# Example.net
KiCad netlist of a schematic drawn in EAGLE
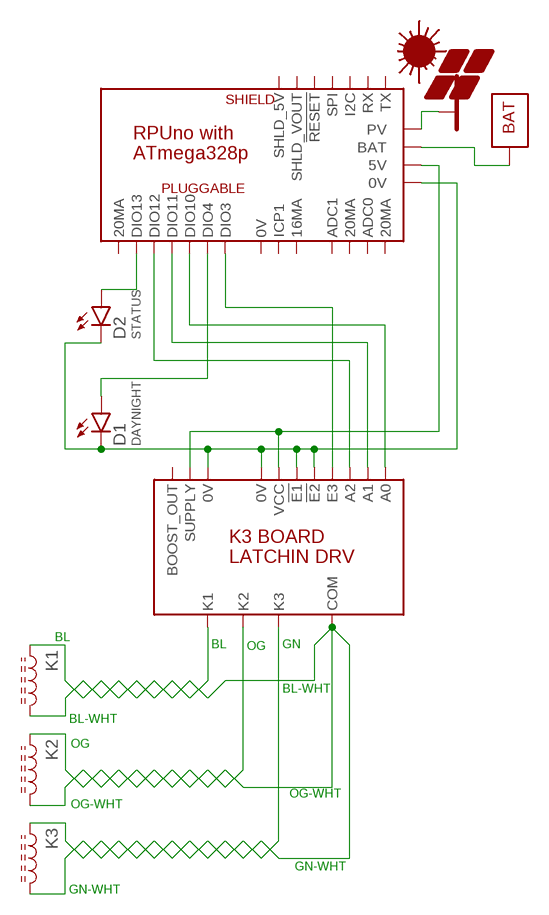
[diagram p0: schematic, sheet 1]

(export (version "E")
  (design (tool "Eeschema 10.0.6"))
  (components
    (comp (ref "BM3")
      (value "RPUNO")
      (footprint "eagle-import:NA-30")
      (libsource (lib "eagle-import") (part "RPUNO"))
    )
    (comp (ref "D1")
      (value "DAYNIGHT")
      (footprint "eagle-import:LED5MM")
      (libsource (lib "eagle-import") (part "LED5MM"))
    )
    (comp (ref "D2")
      (value "STATUS")
      (footprint "eagle-import:LED5MM")
      (libsource (lib "eagle-import") (part "LED5MM"))
    )
    (comp (ref "K1")
      (value "L0805")
      (footprint "eagle-import:C0805(2012)")
      (libsource (lib "eagle-import") (part "L0805"))
    )
    (comp (ref "K2")
      (value "L0805")
      (footprint "eagle-import:C0805(2012)")
      (libsource (lib "eagle-import") (part "L0805"))
    )
    (comp (ref "K3")
      (value "L0805")
      (footprint "eagle-import:C0805(2012)")
      (libsource (lib "eagle-import") (part "L0805"))
    )
    (comp (ref "PV4")
      (value "PV")
      (footprint "eagle-import:NA-30")
      (libsource (lib "eagle-import") (part "PV"))
    )
    (comp (ref "U$1")
      (value "K3")
      (footprint "eagle-import:NA-30")
      (libsource (lib "eagle-import") (part "K3"))
    )
    (comp (ref "U$7")
      (value "BAT")
      (footprint "eagle-import:NA-30")
      (libsource (lib "eagle-import") (part "BAT"))
    )
  )
  (nets
    (net (code "1") (name "/BL") (class "Default")
      (node (ref "K1") (pin "1") (pinfunction "1_1") (pintype "passive"))
      (node (ref "U$1") (pin "11") (pinfunction "K1_11") (pintype "bidirectional"))
    )
    (net (code "2") (name "/BL-WHT") (class "Default")
      (node (ref "K1") (pin "2") (pinfunction "2_2") (pintype "passive"))
      (node (ref "U$1") (pin "9") (pinfunction "COM_9") (pintype "bidirectional"))
    )
    (net (code "3") (name "/GN") (class "Default")
      (node (ref "K3") (pin "1") (pinfunction "1_1") (pintype "passive"))
      (node (ref "U$1") (pin "13") (pinfunction "K3_13") (pintype "bidirectional"))
    )
    (net (code "4") (name "/GN-WHT") (class "Default")
      (node (ref "K3") (pin "2") (pinfunction "2_2") (pintype "passive"))
    )
    (net (code "5") (name "/OG") (class "Default")
      (node (ref "K2") (pin "1") (pinfunction "1_1") (pintype "passive"))
      (node (ref "U$1") (pin "12") (pinfunction "K2_12") (pintype "bidirectional"))
    )
    (net (code "6") (name "/OG-WHT") (class "Default")
      (node (ref "K2") (pin "2") (pinfunction "2_2") (pintype "passive"))
    )
    (net (code "7") (name "Net-(BM3-5V)") (class "Default")
      (node (ref "BM3") (pin "19") (pinfunction "5V_19") (pintype "bidirectional"))
      (node (ref "U$1") (pin "14") (pinfunction "SUPPLY_14") (pintype "bidirectional"))
      (node (ref "U$1") (pin "15") (pinfunction "VCC_15") (pintype "bidirectional"))
    )
    (net (code "8") (name "Net-(BM3-BAT)") (class "Default")
      (node (ref "BM3") (pin "9") (pinfunction "BAT_9") (pintype "bidirectional"))
      (node (ref "U$7") (pin "1") (pinfunction "BAT_PWR_1") (pintype "bidirectional"))
    )
    (net (code "9") (name "Net-(BM3-DIO3)") (class "Default")
      (node (ref "BM3") (pin "13") (pinfunction "DIO3_13") (pintype "bidirectional"))
      (node (ref "U$1") (pin "10") (pinfunction "E3_10") (pintype "bidirectional"))
    )
    (net (code "10") (name "Net-(BM3-DIO4)") (class "Default")
      (node (ref "BM3") (pin "14") (pinfunction "DIO4_14") (pintype "bidirectional"))
      (node (ref "D1") (pin "A") (pinfunction "A_A") (pintype "passive"))
    )
    (net (code "11") (name "Net-(BM3-DIO10)") (class "Default")
      (node (ref "BM3") (pin "15") (pinfunction "DIO10_15") (pintype "bidirectional"))
      (node (ref "U$1") (pin "5") (pinfunction "A0_5") (pintype "bidirectional"))
    )
    (net (code "12") (name "Net-(BM3-DIO11)") (class "Default")
      (node (ref "BM3") (pin "16") (pinfunction "DIO11_16") (pintype "bidirectional"))
      (node (ref "U$1") (pin "6") (pinfunction "A1_6") (pintype "bidirectional"))
    )
    (net (code "13") (name "Net-(BM3-DIO12)") (class "Default")
      (node (ref "BM3") (pin "17") (pinfunction "DIO12_17") (pintype "bidirectional"))
      (node (ref "U$1") (pin "7") (pinfunction "A2_7") (pintype "bidirectional"))
    )
    (net (code "14") (name "Net-(BM3-DIO13)") (class "Default")
      (node (ref "BM3") (pin "18") (pinfunction "DIO13_18") (pintype "bidirectional"))
      (node (ref "D2") (pin "A") (pinfunction "A_A") (pintype "passive"))
    )
    (net (code "15") (name "Net-(BM3-PV)") (class "Default")
      (node (ref "BM3") (pin "8") (pinfunction "PV_8") (pintype "bidirectional"))
      (node (ref "PV4") (pin "1") (pinfunction "PV_PWR_1") (pintype "bidirectional"))
    )
    (net (code "16") (name "Net-(U$1-~{E1})") (class "Default")
      (node (ref "BM3") (pin "20") (pinfunction "0V_20") (pintype "bidirectional"))
      (node (ref "D1") (pin "K") (pinfunction "K_K") (pintype "passive"))
      (node (ref "D2") (pin "K") (pinfunction "K_K") (pintype "passive"))
      (node (ref "U$1") (pin "1") (pinfunction "~{E1}_1") (pintype "bidirectional"))
      (node (ref "U$1") (pin "2") (pinfunction "~{E2}_2") (pintype "bidirectional"))
      (node (ref "U$1") (pin "3") (pinfunction "0V_3") (pintype "bidirectional"))
      (node (ref "U$1") (pin "4") (pinfunction "0V_4") (pintype "bidirectional"))
    )
    (net (code "17") (name "unconnected-(BM3-0V-Pad25)") (class "Default")
      (node (ref "BM3") (pin "25") (pinfunction "0V_25") (pintype "bidirectional"))
    )
    (net (code "18") (name "unconnected-(BM3-16MA-Pad21)") (class "Default")
      (node (ref "BM3") (pin "21") (pinfunction "16MA_21") (pintype "bidirectional"))
    )
    (net (code "19") (name "unconnected-(BM3-20MA-Pad22)") (class "Default")
      (node (ref "BM3") (pin "22") (pinfunction "20MA_22") (pintype "bidirectional"))
    )
    (net (code "20") (name "unconnected-(BM3-20MA-Pad23)") (class "Default")
      (node (ref "BM3") (pin "23") (pinfunction "20MA_23") (pintype "bidirectional"))
    )
    (net (code "21") (name "unconnected-(BM3-20MA-Pad24)") (class "Default")
      (node (ref "BM3") (pin "24") (pinfunction "20MA_24") (pintype "bidirectional"))
    )
    (net (code "22") (name "unconnected-(BM3-ADC0-Pad10)") (class "Default")
      (node (ref "BM3") (pin "10") (pinfunction "ADC0_10") (pintype "bidirectional"))
    )
    (net (code "23") (name "unconnected-(BM3-ADC1-Pad11)") (class "Default")
      (node (ref "BM3") (pin "11") (pinfunction "ADC1_11") (pintype "bidirectional"))
    )
    (net (code "24") (name "unconnected-(BM3-I2C-Pad3)") (class "Default")
      (node (ref "BM3") (pin "3") (pinfunction "I2C_3") (pintype "bidirectional"))
    )
    (net (code "25") (name "unconnected-(BM3-ICP1-Pad12)") (class "Default")
      (node (ref "BM3") (pin "12") (pinfunction "ICP1_12") (pintype "bidirectional"))
    )
    (net (code "26") (name "unconnected-(BM3-RX-Pad2)") (class "Default")
      (node (ref "BM3") (pin "2") (pinfunction "RX_2") (pintype "bidirectional"))
    )
    (net (code "27") (name "unconnected-(BM3-SHLD_5V-Pad6)") (class "Default")
      (node (ref "BM3") (pin "6") (pinfunction "SHLD_5V_6") (pintype "bidirectional"))
    )
    (net (code "28") (name "unconnected-(BM3-SHLD_VOUT-Pad7)") (class "Default")
      (node (ref "BM3") (pin "7") (pinfunction "SHLD_VOUT_7") (pintype "bidirectional"))
    )
    (net (code "29") (name "unconnected-(BM3-SPI-Pad4)") (class "Default")
      (node (ref "BM3") (pin "4") (pinfunction "SPI_4") (pintype "bidirectional"))
    )
    (net (code "30") (name "unconnected-(BM3-TX-Pad1)") (class "Default")
      (node (ref "BM3") (pin "1") (pinfunction "TX_1") (pintype "bidirectional"))
    )
    (net (code "31") (name "unconnected-(BM3-~{RESET}-Pad5)") (class "Default")
      (node (ref "BM3") (pin "5") (pinfunction "~{RESET}_5") (pintype "bidirectional"))
    )
    (net (code "32") (name "unconnected-(U$1-BOOST_OUT-Pad8)") (class "Default")
      (node (ref "U$1") (pin "8") (pinfunction "BOOST_OUT_8") (pintype "bidirectional"))
    )
  )
)
